# LCL_TempSensor.net
KiCad netlist of a schematic drawn in Altium Designer
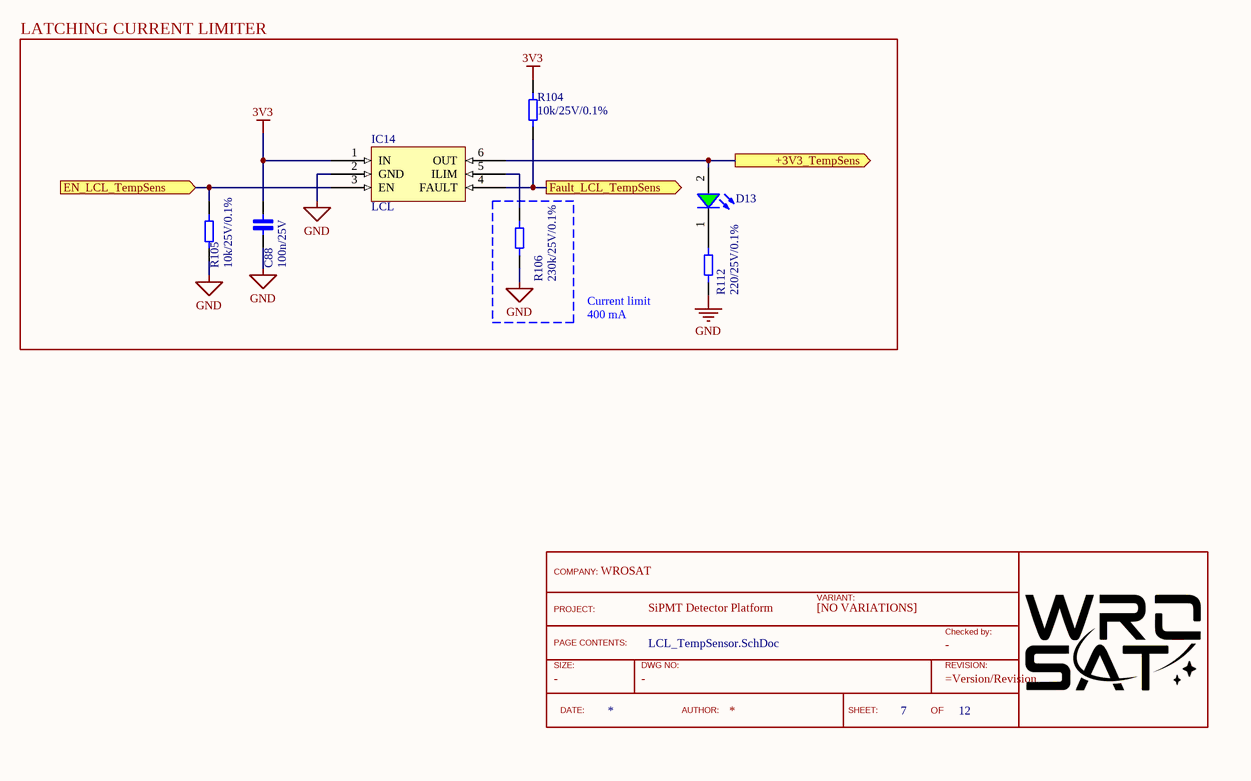
[diagram p0: LCL_TempSensor.SchDoc]

(export (version "E")
  (design (tool "Eeschema 10.0.6"))
  (components
    (comp (ref "C88")
      (value "100n/25V")
      (footprint "Cap_0402")
      (description "Ceramic Capacitor 100n / 0402 / 25V / ±5%, Wurth Elektronik MLCC")
      (libsource (lib "Cubesat_lib") (part "Cap_0402_100n"))
    )
    (comp (ref "D13")
      (value "Green, 3.2V")
      (footprint "WL-SMCW_0603_H=0.7mm")
      (description "WL-SMCW SMT Mono-color Chip LED Waterclear, size 0603, Green, 3.2V, 140deg")
      (fields (field (name "PART NUMBER") "150060GS75000") (field (name "PUBLISHER") "Wurth Elektronik"))
      (libsource (lib "LEDS") (part "150060GS75000"))
    )
    (comp (ref "IC14")
      (value "LCL")
      (footprint "SOT-23-6")
      (description "Latch-off Current Limiter")
      (libsource (lib "Cubesat_lib") (part "TPS2553"))
    )
    (comp (ref "R104")
      (value "10k/25V/0.1%")
      (footprint "RES_0402")
      (description "Vishay, thin film resistor 10k/25V/0.1%")
      (libsource (lib "Cubesat_lib") (part "Res_0402_10k"))
    )
    (comp (ref "R105")
      (value "10k/25V/0.1%")
      (footprint "RES_0402")
      (description "Vishay, thin film resistor 10k/25V/0.1%")
      (libsource (lib "Cubesat_lib") (part "Res_0402_10k"))
    )
    (comp (ref "R106")
      (value "230k/25V/0.1%")
      (footprint "RES_0402")
      (description "Vishay, thin film resistor 230k/25V/0.1%")
      (libsource (lib "Cubesat_lib") (part "Res_0402_230k"))
    )
    (comp (ref "R112")
      (value "220/25V/0.1%")
      (footprint "RES_0402")
      (description "Vishay, thin film resistor 1/25V/0.1%")
      (libsource (lib "Cubesat_lib") (part "Res_0402_1"))
    )
  )
  (nets
    (net (code "1") (name "/+3V3_TempSens") (class "Default")
      (node (ref "D13") (pin "2") (pinfunction "A_2") (pintype "passive"))
      (node (ref "IC14") (pin "6") (pinfunction "OUT_6") (pintype "input"))
    )
    (net (code "2") (name "/EN_LCL_TempSens") (class "Default")
      (node (ref "IC14") (pin "3") (pinfunction "EN_3") (pintype "input"))
      (node (ref "R105") (pin "2") (pinfunction "2_2") (pintype "passive"))
    )
    (net (code "3") (name "/Fault_LCL_TempSens") (class "Default")
      (node (ref "IC14") (pin "4") (pinfunction "FAULT_4") (pintype "input"))
      (node (ref "R104") (pin "1") (pinfunction "1_1") (pintype "passive"))
    )
    (net (code "4") (name "3V3") (class "Default")
      (node (ref "C88") (pin "2") (pinfunction "2_2") (pintype "passive"))
      (node (ref "IC14") (pin "1") (pinfunction "IN_1") (pintype "input"))
      (node (ref "R104") (pin "2") (pinfunction "2_2") (pintype "passive"))
    )
    (net (code "5") (name "GND") (class "Default")
      (node (ref "C88") (pin "1") (pinfunction "1_1") (pintype "passive"))
      (node (ref "IC14") (pin "2") (pinfunction "GND_2") (pintype "input"))
      (node (ref "R105") (pin "1") (pinfunction "1_1") (pintype "passive"))
      (node (ref "R106") (pin "1") (pinfunction "1_1") (pintype "passive"))
      (node (ref "R112") (pin "1") (pinfunction "1_1") (pintype "passive"))
    )
    (net (code "6") (name "Net-(D13-K)") (class "Default")
      (node (ref "D13") (pin "1") (pinfunction "K_1") (pintype "passive"))
      (node (ref "R112") (pin "2") (pinfunction "2_2") (pintype "passive"))
    )
    (net (code "7") (name "Net-(IC14-ILIM)") (class "Default")
      (node (ref "IC14") (pin "5") (pinfunction "ILIM_5") (pintype "input"))
      (node (ref "R106") (pin "2") (pinfunction "2_2") (pintype "passive"))
    )
  )
)
